# Power_Managment.net
KiCad netlist of a schematic drawn in Altium Designer
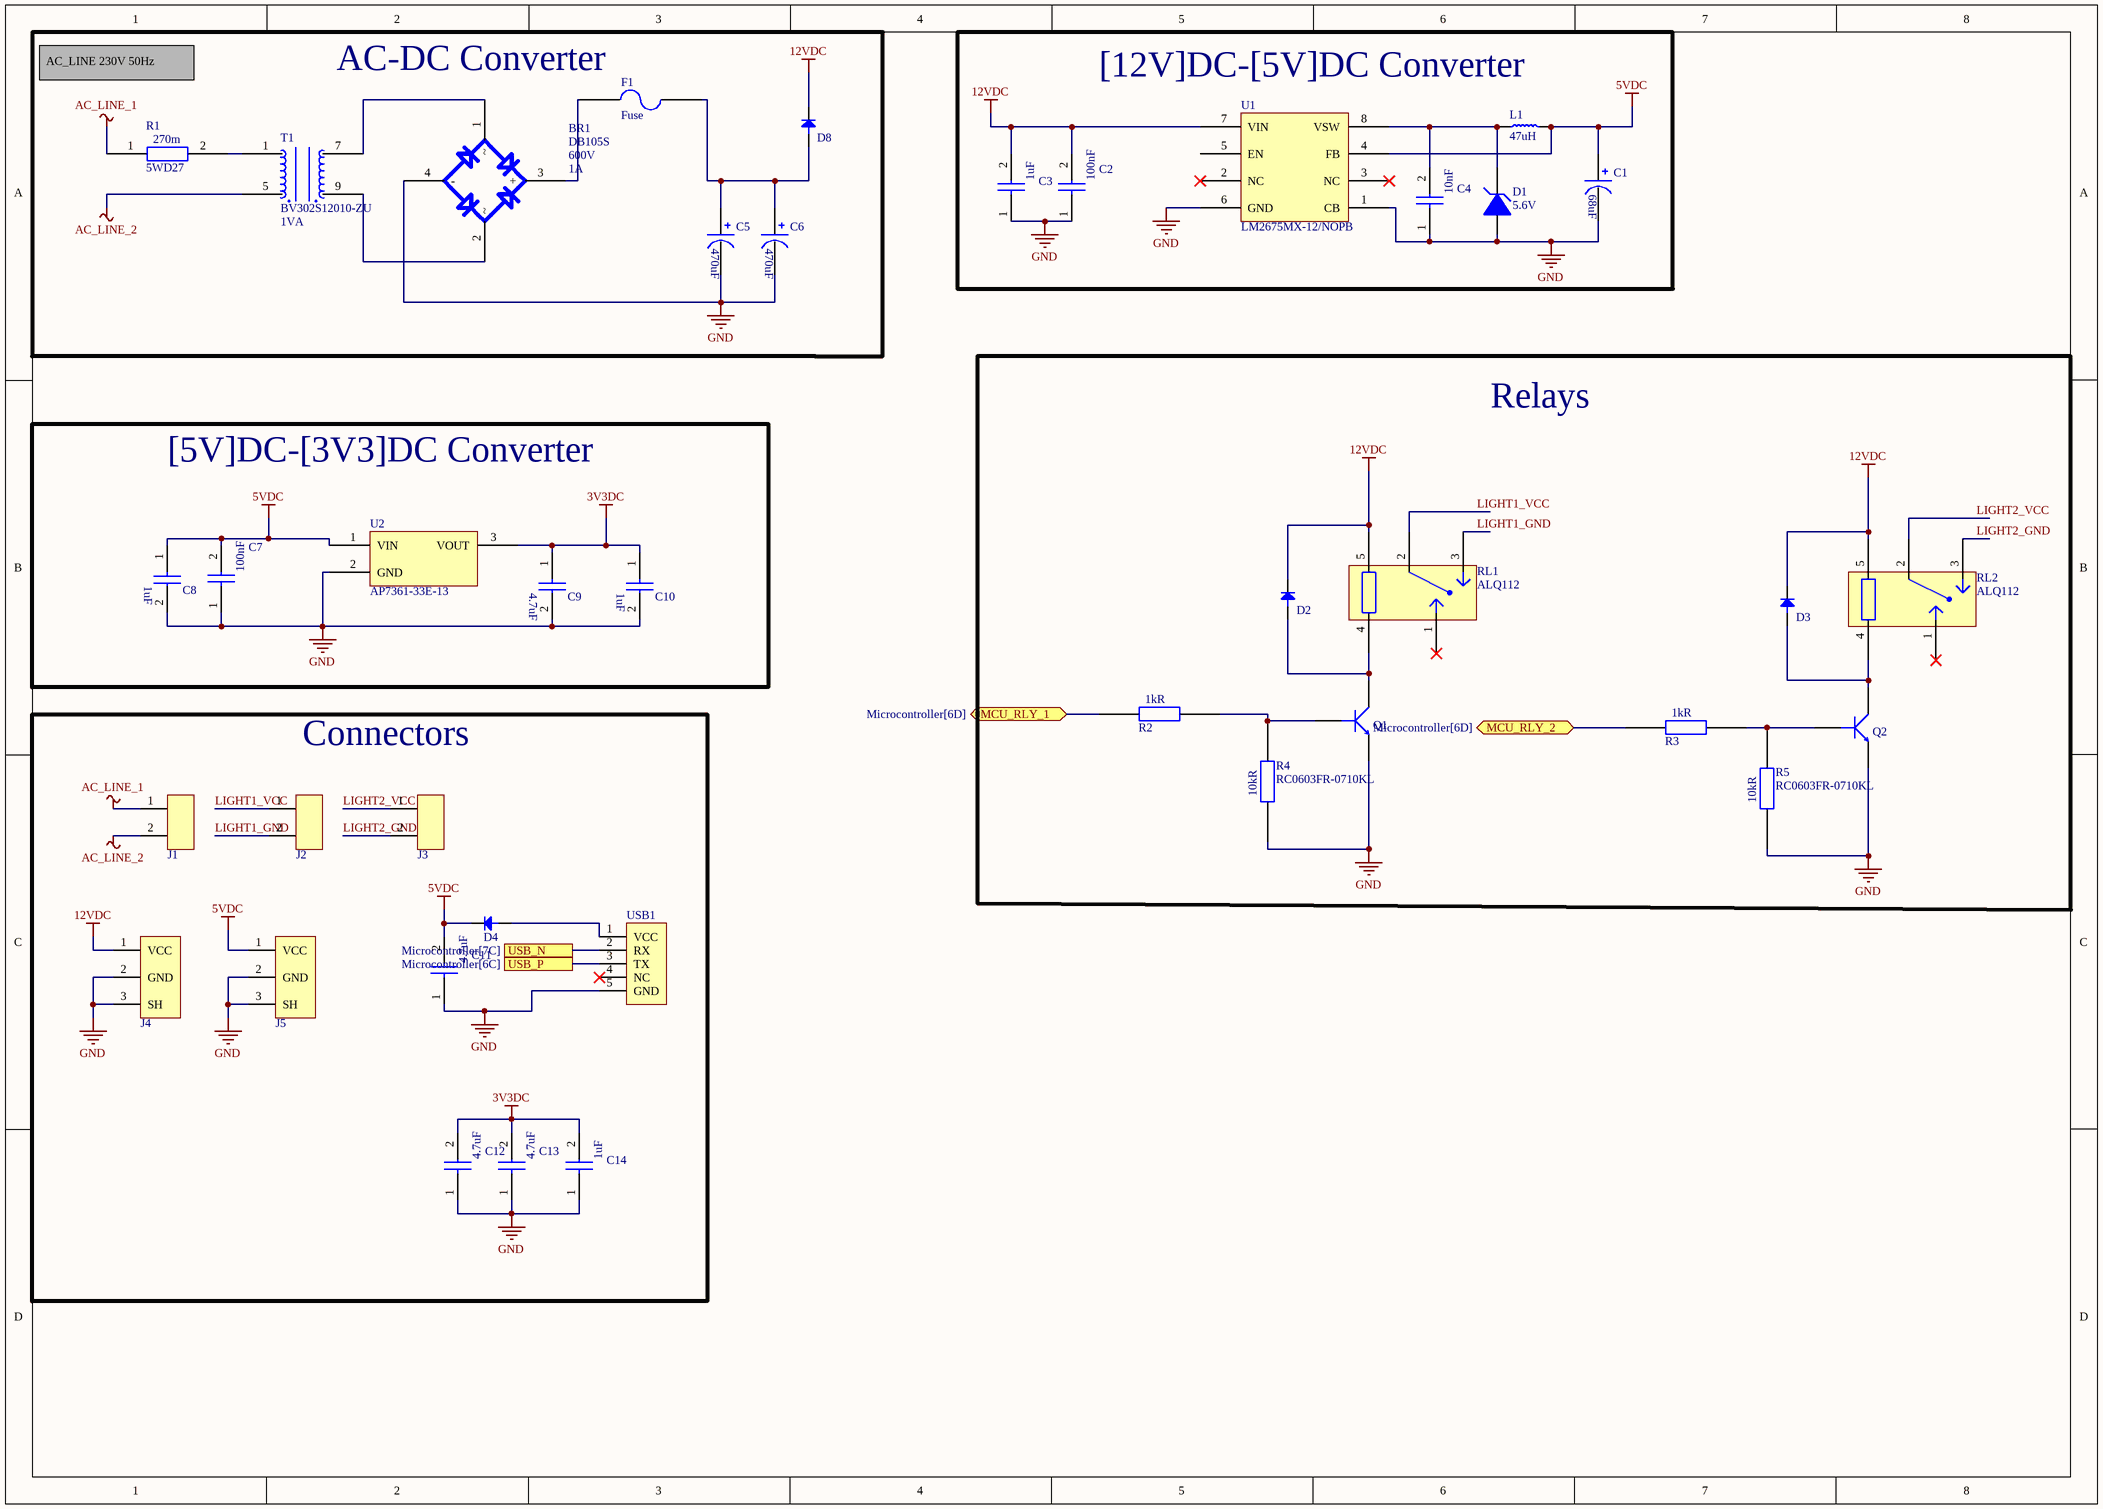
[diagram p0: Power Managment.SchDoc]

(export (version "E")
  (design (tool "Eeschema 10.0.6"))
  (components
    (comp (ref "BR1")
      (value "DB105S")
      (footprint "DB-S")
      (description "Bridge Rect 1PHASE 600V 1A Db-s")
      (fields
        (field (name "MANUFACTURER") "Sangdest Microelectronics")
        (field (name "OPERATION VOLTAGE") "600V")
        (field (name "MAX CURRENT") "1A")
      )
      (libsource (lib "bowtie") (part "DB105S"))
    )
    (comp (ref "C1")
      (value "EEV686M035A9HAA")
      (footprint "EEV 6,3X7,7")
      (description "Cap Aluminum Lytic 68uF 35V 20% (6.3 X 7.7mm) SMD 280mA 2000h 105C T/R")
      (libsource (lib "bowtie") (part "CAP ALU ELEC 68uF 35V %20"))
    )
    (comp (ref "C2")
      (value "CL21B104KBCNNNC")
      (footprint "CAP_0805")
      (description "CAP CER 100nF %10 0603 SMD")
      (fields
        (field (name "MANUFACTURER") "Samsung")
        (field (name "TOLERANCE") "10%")
        (field (name "DESIGNED BY") "BERK")
      )
      (libsource (lib "bowtie") (part "CAP CER 0805 100nF %10"))
    )
    (comp (ref "C3")
      (value "CL21B105KBFNNNE")
      (footprint "CAP_0805")
      (description "CAP CER 1uF %10 0805")
      (fields
        (field (name "MANUFACTURER") "Samsung")
        (field (name "TOLERANCE") "10%")
        (field (name "DESIGNED BY") "BERK")
      )
      (libsource (lib "bowtie") (part "CAP CER 0805 1uF %10"))
    )
    (comp (ref "C4")
      (value "0603B103K160CT")
      (footprint "CAP_0603")
      (description "CAP CER 10nF %10 0603")
      (fields
        (field (name "MANUFACTURER") "Walsin Technologies")
        (field (name "TOLERANCE") "10%")
        (field (name "DESIGNED BY") "BERK")
      )
      (libsource (lib "bowtie") (part "CAP CER 0603 10nF %10"))
    )
    (comp (ref "C5")
      (value "~")
      (footprint "CAP_RADIAL_D10_P5")
      (description "Cap, 470UF, 50V, Alu Elec, Radial")
      (fields
        (field (name "MANUFACTURER") "KEMET")
        (field (name "MANUFACTURER PART NUMBER") "ESH477M050AH4AA")
        (field (name "DESIGNED BY") "Mert Ali Şentürk")
      )
      (libsource (lib "bowtie") (part "CAP ALU ELEC 470uF 50V"))
    )
    (comp (ref "C6")
      (value "~")
      (footprint "CAP_RADIAL_D10_P5")
      (description "Cap, 470UF, 50V, Alu Elec, Radial")
      (fields
        (field (name "MANUFACTURER") "KEMET")
        (field (name "MANUFACTURER PART NUMBER") "ESH477M050AH4AA")
        (field (name "DESIGNED BY") "Mert Ali Şentürk")
      )
      (libsource (lib "bowtie") (part "CAP ALU ELEC 470uF 50V"))
    )
    (comp (ref "C7")
      (value "C0603C104K5RACTU")
      (footprint "CAP_0603")
      (description "Multilayer Ceramic Capacitor, 0.1 uF, 50 V, ± 10%, X7R, 0603 [1608 Metric]")
      (fields
        (field (name "MANUFACTURER") "KEMET")
        (field (name "TOLERANCE") "10%")
        (field (name "DESIGNED BY") "Mert Ali Şentürk")
      )
      (libsource (lib "bowtie") (part "CAP CER 0603 100nF %10"))
    )
    (comp (ref "C8")
      (value "CL21B105KBFNNNE")
      (footprint "CAP_0805")
      (description "CAP CER 1uF %10 0805")
      (fields
        (field (name "MANUFACTURER") "Samsung")
        (field (name "TOLERANCE") "10%")
        (field (name "DESIGNED BY") "BERK")
      )
      (libsource (lib "bowtie") (part "CAP CER 0805 1uF %10"))
    )
    (comp (ref "C9")
      (value "CL21A475KAQNNNE")
      (footprint "CAP_0805")
      (description "CAP CER 4.7uF %10 0805")
      (fields
        (field (name "MANUFACTURER") "Samsung")
        (field (name "TOLERANCE") "10%")
        (field (name "DESIGNED BY") "BERK")
      )
      (libsource (lib "bowtie") (part "CAP CER 0805 4.7uF %10"))
    )
    (comp (ref "C10")
      (value "CL21B105KBFNNNE")
      (footprint "CAP_0805")
      (description "CAP CER 1uF %10 0805")
      (fields
        (field (name "MANUFACTURER") "Samsung")
        (field (name "TOLERANCE") "10%")
        (field (name "DESIGNED BY") "BERK")
      )
      (libsource (lib "bowtie") (part "CAP CER 0805 1uF %10"))
    )
    (comp (ref "C11")
      (value "CL21A475KAQNNNE")
      (footprint "CAP_0805")
      (description "CAP CER 4.7uF %10 0805")
      (fields
        (field (name "MANUFACTURER") "Samsung")
        (field (name "TOLERANCE") "10%")
        (field (name "DESIGNED BY") "BERK")
      )
      (libsource (lib "bowtie") (part "CAP CER 0805 4.7uF %10"))
    )
    (comp (ref "C12")
      (value "CL21A475KAQNNNE")
      (footprint "CAP_0805")
      (description "CAP CER 4.7uF %10 0805")
      (fields
        (field (name "MANUFACTURER") "Samsung")
        (field (name "TOLERANCE") "10%")
        (field (name "DESIGNED BY") "BERK")
      )
      (libsource (lib "bowtie") (part "CAP CER 0805 4.7uF %10"))
    )
    (comp (ref "C13")
      (value "CL21A475KAQNNNE")
      (footprint "CAP_0805")
      (description "CAP CER 4.7uF %10 0805")
      (fields
        (field (name "MANUFACTURER") "Samsung")
        (field (name "TOLERANCE") "10%")
        (field (name "DESIGNED BY") "BERK")
      )
      (libsource (lib "bowtie") (part "CAP CER 0805 4.7uF %10"))
    )
    (comp (ref "C14")
      (value "CL21B105KBFNNNE")
      (footprint "CAP_0805")
      (description "CAP CER 1uF %10 0805")
      (fields
        (field (name "MANUFACTURER") "Samsung")
        (field (name "TOLERANCE") "10%")
        (field (name "DESIGNED BY") "BERK")
      )
      (libsource (lib "bowtie") (part "CAP CER 0805 1uF %10"))
    )
    (comp (ref "D1")
      (value "1SMB5919BT3G")
      (footprint "DO-214AA/SMB")
      (description "Diode Zener Single 5.6V 5% 3W 2-Pin SMB T/R")
      (fields
        (field (name "MANUFACTURER") "ON Semiconductor")
        (field (name "TOLERANCE") "5%")
        (field (name "WORKING VOLTAGE") "5.6V")
        (field (name "DESIGNED BY") "BERK")
      )
      (libsource (lib "bowtie") (part "1SMB5919BT3G"))
    )
    (comp (ref "D2")
      (value "1N4148WS")
      (footprint "SOD-323F")
      (description "Diode, Single, 75 V, 150 mA, 1 V, 4 ns")
      (fields
        (field (name "MANUFACTURER") "ON Semiconductor / Fairchild")
        (field (name "DESIGNED BY") "BERK")
      )
      (libsource (lib "bowtie") (part "1N4148WS"))
    )
    (comp (ref "D3")
      (value "1N4148WS")
      (footprint "SOD-323F")
      (description "Diode, Single, 75 V, 150 mA, 1 V, 4 ns")
      (fields
        (field (name "MANUFACTURER") "ON Semiconductor / Fairchild")
        (field (name "DESIGNED BY") "BERK")
      )
      (libsource (lib "bowtie") (part "1N4148WS"))
    )
    (comp (ref "D4")
      (value "1N4148WS")
      (footprint "SOD-323F")
      (description "Diode, Single, 75 V, 150 mA, 1 V, 4 ns")
      (fields
        (field (name "MANUFACTURER") "ON Semiconductor / Fairchild")
        (field (name "DESIGNED BY") "BERK")
      )
      (libsource (lib "bowtie") (part "1N4148WS"))
    )
    (comp (ref "D8")
      (value "1N4148WS")
      (footprint "SOD-323F")
      (description "Diode, Single, 75 V, 150 mA, 1 V, 4 ns")
      (fields
        (field (name "MANUFACTURER") "ON Semiconductor / Fairchild")
        (field (name "DESIGNED BY") "BERK")
      )
      (libsource (lib "bowtie") (part "1N4148WS"))
    )
    (comp (ref "F1") (value "Fuse") (footprint "3413.0216.22") (libsource (lib "bowtie") (part "Fuse")))
    (comp (ref "J1")
      (value "TBP01R1-508-02BE")
      (footprint "TBP01R1-508")
      (description "Conn Shrouded Header HDR 2 POS 5.08mm Solder RA Side Entry Thru-Hole Bag")
      (fields (field (name "MANUFACTURER") "CUI") (field (name "DESIGNED BY") "BERK"))
      (libsource (lib "bowtie") (part "TBP01R1-508-02BE"))
    )
    (comp (ref "J2")
      (value "TBP01R1-508-02BE")
      (footprint "TBP01R1-508")
      (description "Conn Shrouded Header HDR 2 POS 5.08mm Solder RA Side Entry Thru-Hole Bag")
      (fields (field (name "MANUFACTURER") "CUI") (field (name "DESIGNED BY") "BERK"))
      (libsource (lib "bowtie") (part "TBP01R1-508-02BE"))
    )
    (comp (ref "J3")
      (value "TBP01R1-508-02BE")
      (footprint "TBP01R1-508")
      (description "Conn Shrouded Header HDR 2 POS 5.08mm Solder RA Side Entry Thru-Hole Bag")
      (fields (field (name "MANUFACTURER") "CUI") (field (name "DESIGNED BY") "BERK"))
      (libsource (lib "bowtie") (part "TBP01R1-508-02BE"))
    )
    (comp (ref "J4")
      (value "PJ-037AH-SMT-TR")
      (footprint "JACK")
      (description "DC Power Connectors Power Jacks")
      (fields (field (name "MANUFACTURER") "CUI") (field (name "DESIGNED BY") "BERK"))
      (libsource (lib "bowtie") (part "PJ-037AH-SMT-TR"))
    )
    (comp (ref "J5")
      (value "PJ-037AH-SMT-TR")
      (footprint "JACK")
      (description "DC Power Connectors Power Jacks")
      (fields (field (name "MANUFACTURER") "CUI") (field (name "DESIGNED BY") "BERK"))
      (libsource (lib "bowtie") (part "PJ-037AH-SMT-TR"))
    )
    (comp (ref "L1")
      (value "78438335470")
      (footprint "INDUCTOR 78438335470")
      (description "FIXED IND 47UH 390MA 2.3 OHM SMD")
      (fields
        (field (name "MANUFACTURER") "Wurth Electronics")
        (field (name "TOLERANCE") "30%")
        (field (name "INDUCTANCE") "47uH")
        (field (name "DESIGNED BY") "BERK")
      )
      (libsource (lib "bowtie") (part "IND 47uH"))
    )
    (comp (ref "Q1")
      (value "MMBT3904-7-F")
      (footprint "SOT23-F")
      (description "Transistor General Purpose BJT NPN 40 Volt 0.2A Automotive 3-Pin SOT-23")
      (fields (field (name "MANUFACTURER") "Diodes Zetex") (field (name "DESIGNED BY") "BERK"))
      (libsource (lib "bowtie") (part "MMBT3904-7-F"))
    )
    (comp (ref "Q2")
      (value "MMBT3904-7-F")
      (footprint "SOT23-F")
      (description "Transistor General Purpose BJT NPN 40 Volt 0.2A Automotive 3-Pin SOT-23")
      (fields (field (name "MANUFACTURER") "Diodes Zetex") (field (name "DESIGNED BY") "BERK"))
      (libsource (lib "bowtie") (part "MMBT3904-7-F"))
    )
    (comp (ref "R1")
      (value "5WD27")
      (footprint "RES_AXIAL_W")
      (description "Resistor 5 Watt Cermet Wirewound Flameproof .27 Ohm 5% Axial Lead")
      (libsource (lib "bowtie") (part "5WD27"))
    )
    (comp (ref "R2")
      (value "RC0603FR-0710KL")
      (footprint "RES_0603")
      (description "RES 1K %1 OHM 0603 SMD")
      (fields
        (field (name "MANUFACTURER") "Yageo")
        (field (name "MANUFACTURER PART NUMBER") "RC0603JR-071KL")
        (field (name "DESIGNED BY") "BERK")
      )
      (libsource (lib "bowtie") (part "RES 0603 1kR %1"))
    )
    (comp (ref "R3")
      (value "RC0603FR-0710KL")
      (footprint "RES_0603")
      (description "RES 1K %1 OHM 0603 SMD")
      (fields
        (field (name "MANUFACTURER") "Yageo")
        (field (name "MANUFACTURER PART NUMBER") "RC0603JR-071KL")
        (field (name "DESIGNED BY") "BERK")
      )
      (libsource (lib "bowtie") (part "RES 0603 1kR %1"))
    )
    (comp (ref "R4")
      (value "RC0603FR-0710KL")
      (footprint "RES_0603")
      (description "RES 10K %1 OHM 0603 SMD")
      (fields (field (name "DESIGNED BY") "Mert Ali Şentürk"))
      (libsource (lib "bowtie") (part "RES 0603 10kR %1"))
    )
    (comp (ref "R5")
      (value "RC0603FR-0710KL")
      (footprint "RES_0603")
      (description "RES 10K %1 OHM 0603 SMD")
      (fields (field (name "DESIGNED BY") "Mert Ali Şentürk"))
      (libsource (lib "bowtie") (part "RES 0603 10kR %1"))
    )
    (comp (ref "RL1")
      (value "ALQ112")
      (footprint "ALQ112")
      (description "Electromechanical Relay 12VDC 360Ohm 10(NO)/3(NC)A SPDT (( 20mm 10mm 16mm)) THT Power Relay")
      (fields (field (name "MANUFACTURER") "Panasonic") (field (name "DESIGNED BY") "Mert Ali Şentürk"))
      (libsource (lib "bowtie") (part "ALQ112"))
    )
    (comp (ref "RL2")
      (value "ALQ112")
      (footprint "ALQ112")
      (description "Electromechanical Relay 12VDC 360Ohm 10(NO)/3(NC)A SPDT (( 20mm 10mm 16mm)) THT Power Relay")
      (fields (field (name "MANUFACTURER") "Panasonic") (field (name "DESIGNED BY") "Mert Ali Şentürk"))
      (libsource (lib "bowtie") (part "ALQ112"))
    )
    (comp (ref "T1")
      (value "BV302S12010-ZU")
      (footprint "BV302S12010")
      (description "PWR XFMR LAMINATED 1VA TH")
      (fields (field (name "RATED POWER") "1VA") (field (name "DESIGNED BY") "Mert Ali Şentürk"))
      (libsource (lib "bowtie") (part "BV302S12010-ZU"))
    )
    (comp (ref "U1")
      (value "LM2675MX-12/NOPB")
      (footprint "SOIC-8")
      (description "SIMPLE SWITCHER® 6.5V to 40V, 1A Low Component Count Step-Down Regulator 8-SOIC -40 to 125")
      (fields
        (field (name "MANUFACTURER") "TI National Semiconductor")
        (field (name "DESIGNED BY") "Mert Ali Şentürk")
      )
      (libsource (lib "bowtie") (part "LM2675MX-12/NOPB"))
    )
    (comp (ref "U2")
      (value "AP7361-33E-13")
      (footprint "SOT223")
      (description "AP7361 Series 3.3 V 1 A Low SMT Dropout Fixed-Mode Regulator - SOT-223")
      (fields (field (name "MANUFACTURER") "Diodes") (field (name "DESIGNED BY") "Mert Ali Şentürk"))
      (libsource (lib "bowtie") (part "AP7361-33E-13"))
    )
    (comp (ref "USB1")
      (value "10118192-0001LF")
      (footprint "MICRO_B_USB")
      (description "CONN RCPT USB2.0 MICRO B SMD R/A")
      (libsource (lib "bowtie") (part "Micro B USB Connector"))
    )
  )
  (nets
    (net (code "1") (name "/LIGHT1_GND") (class "Default")
      (node (ref "J2") (pin "2") (pinfunction "2_2") (pintype "power_in"))
      (node (ref "RL1") (pin "3") (pinfunction "3_3") (pintype "passive"))
    )
    (net (code "2") (name "/LIGHT1_VCC") (class "Default")
      (node (ref "J2") (pin "1") (pinfunction "1_1") (pintype "power_in"))
      (node (ref "RL1") (pin "2") (pinfunction "2_2") (pintype "passive"))
    )
    (net (code "3") (name "/LIGHT2_GND") (class "Default")
      (node (ref "J3") (pin "2") (pinfunction "2_2") (pintype "power_in"))
      (node (ref "RL2") (pin "3") (pinfunction "3_3") (pintype "passive"))
    )
    (net (code "4") (name "/LIGHT2_VCC") (class "Default")
      (node (ref "J3") (pin "1") (pinfunction "1_1") (pintype "power_in"))
      (node (ref "RL2") (pin "2") (pinfunction "2_2") (pintype "passive"))
    )
    (net (code "5") (name "/MCU_RLY_1") (class "Default")
      (node (ref "R2") (pin "1") (pinfunction "1_1") (pintype "passive"))
    )
    (net (code "6") (name "/MCU_RLY_2") (class "Default")
      (node (ref "R3") (pin "1") (pinfunction "1_1") (pintype "passive"))
    )
    (net (code "7") (name "/USB_N") (class "Default")
      (node (ref "USB1") (pin "2") (pinfunction "RX_2") (pintype "passive"))
    )
    (net (code "8") (name "/USB_P") (class "Default")
      (node (ref "USB1") (pin "3") (pinfunction "TX_3") (pintype "passive"))
    )
    (net (code "9") (name "3V3DC") (class "Default")
      (node (ref "C10") (pin "1") (pinfunction "1_1") (pintype "passive"))
      (node (ref "C12") (pin "2") (pinfunction "2_2") (pintype "passive"))
      (node (ref "C13") (pin "2") (pinfunction "2_2") (pintype "passive"))
      (node (ref "C14") (pin "2") (pinfunction "2_2") (pintype "passive"))
      (node (ref "C9") (pin "1") (pinfunction "1_1") (pintype "passive"))
      (node (ref "U2") (pin "3") (pinfunction "VOUT_3") (pintype "passive"))
    )
    (net (code "10") (name "5VDC") (class "Default")
      (node (ref "C1") (pin "1") (pinfunction "1_1") (pintype "passive"))
      (node (ref "C11") (pin "2") (pinfunction "2_2") (pintype "passive"))
      (node (ref "C7") (pin "2") (pinfunction "2_2") (pintype "passive"))
      (node (ref "C8") (pin "1") (pinfunction "1_1") (pintype "passive"))
      (node (ref "D4") (pin "1") (pinfunction "1_1") (pintype "passive"))
      (node (ref "J5") (pin "1") (pinfunction "VCC_1") (pintype "power_in"))
      (node (ref "L1") (pin "2") (pinfunction "2_2") (pintype "passive"))
      (node (ref "U1") (pin "4") (pinfunction "FB_4") (pintype "passive"))
      (node (ref "U2") (pin "1") (pinfunction "VIN_1") (pintype "passive"))
    )
    (net (code "11") (name "12VDC") (class "Default")
      (node (ref "C2") (pin "2") (pinfunction "2_2") (pintype "passive"))
      (node (ref "C3") (pin "2") (pinfunction "2_2") (pintype "passive"))
      (node (ref "D2") (pin "1") (pinfunction "1_1") (pintype "passive"))
      (node (ref "D3") (pin "1") (pinfunction "1_1") (pintype "passive"))
      (node (ref "D8") (pin "1") (pinfunction "1_1") (pintype "passive"))
      (node (ref "J4") (pin "1") (pinfunction "VCC_1") (pintype "power_in"))
      (node (ref "RL1") (pin "5") (pinfunction "5_5") (pintype "passive"))
      (node (ref "RL2") (pin "5") (pinfunction "5_5") (pintype "passive"))
      (node (ref "U1") (pin "7") (pinfunction "VIN_7") (pintype "passive"))
    )
    (net (code "12") (name "AC_LINE_1") (class "Default")
      (node (ref "J1") (pin "1") (pinfunction "1_1") (pintype "power_in"))
      (node (ref "R1") (pin "1") (pinfunction "1_1") (pintype "passive"))
    )
    (net (code "13") (name "AC_LINE_2") (class "Default")
      (node (ref "J1") (pin "2") (pinfunction "2_2") (pintype "power_in"))
      (node (ref "T1") (pin "5") (pinfunction "5_5") (pintype "passive"))
    )
    (net (code "14") (name "GND") (class "Default")
      (node (ref "BR1") (pin "4") (pinfunction "-_4") (pintype "passive"))
      (node (ref "C1") (pin "2") (pinfunction "2_2") (pintype "passive"))
      (node (ref "C10") (pin "2") (pinfunction "2_2") (pintype "passive"))
      (node (ref "C11") (pin "1") (pinfunction "1_1") (pintype "passive"))
      (node (ref "C12") (pin "1") (pinfunction "1_1") (pintype "passive"))
      (node (ref "C13") (pin "1") (pinfunction "1_1") (pintype "passive"))
      (node (ref "C14") (pin "1") (pinfunction "1_1") (pintype "passive"))
      (node (ref "C2") (pin "1") (pinfunction "1_1") (pintype "passive"))
      (node (ref "C3") (pin "1") (pinfunction "1_1") (pintype "passive"))
      (node (ref "C4") (pin "1") (pinfunction "1_1") (pintype "passive"))
      (node (ref "C5") (pin "2") (pinfunction "2_2") (pintype "passive"))
      (node (ref "C6") (pin "2") (pinfunction "2_2") (pintype "passive"))
      (node (ref "C7") (pin "1") (pinfunction "1_1") (pintype "passive"))
      (node (ref "C8") (pin "2") (pinfunction "2_2") (pintype "passive"))
      (node (ref "C9") (pin "2") (pinfunction "2_2") (pintype "passive"))
      (node (ref "D1") (pin "2") (pinfunction "2_2") (pintype "passive"))
      (node (ref "J4") (pin "2") (pinfunction "GND_2") (pintype "power_in"))
      (node (ref "J4") (pin "3") (pinfunction "SH_3") (pintype "power_in"))
      (node (ref "J5") (pin "2") (pinfunction "GND_2") (pintype "power_in"))
      (node (ref "J5") (pin "3") (pinfunction "SH_3") (pintype "power_in"))
      (node (ref "Q1") (pin "2") (pinfunction "E_2") (pintype "power_in"))
      (node (ref "Q2") (pin "2") (pinfunction "E_2") (pintype "power_in"))
      (node (ref "R4") (pin "1") (pinfunction "1_1") (pintype "passive"))
      (node (ref "R5") (pin "1") (pinfunction "1_1") (pintype "passive"))
      (node (ref "U1") (pin "1") (pinfunction "CB_1") (pintype "passive"))
      (node (ref "U1") (pin "6") (pinfunction "GND_6") (pintype "passive"))
      (node (ref "U2") (pin "2") (pinfunction "GND_2") (pintype "passive"))
      (node (ref "USB1") (pin "5") (pinfunction "GND_5") (pintype "passive"))
    )
    (net (code "15") (name "Net-(BR1-+)") (class "Default")
      (node (ref "BR1") (pin "3") (pinfunction "+_3") (pintype "passive"))
      (node (ref "F1") (pin "1") (pinfunction "1_1") (pintype "passive"))
    )
    (net (code "16") (name "Net-(BR1-~-Pad1)") (class "Default")
      (node (ref "BR1") (pin "1") (pinfunction "~_1") (pintype "passive"))
      (node (ref "T1") (pin "7") (pinfunction "7_7") (pintype "passive"))
    )
    (net (code "17") (name "Net-(BR1-~-Pad2)") (class "Default")
      (node (ref "BR1") (pin "2") (pinfunction "~_2") (pintype "passive"))
      (node (ref "T1") (pin "9") (pinfunction "9_9") (pintype "passive"))
    )
    (net (code "18") (name "Net-(C5-Pad1)") (class "Default")
      (node (ref "C5") (pin "1") (pinfunction "1_1") (pintype "passive"))
      (node (ref "C6") (pin "1") (pinfunction "1_1") (pintype "passive"))
      (node (ref "D8") (pin "2") (pinfunction "2_2") (pintype "passive"))
      (node (ref "F1") (pin "2") (pinfunction "2_2") (pintype "passive"))
    )
    (net (code "19") (name "Net-(Q1-B)") (class "Default")
      (node (ref "Q1") (pin "1") (pinfunction "B_1") (pintype "power_in"))
      (node (ref "R2") (pin "2") (pinfunction "2_2") (pintype "passive"))
      (node (ref "R4") (pin "2") (pinfunction "2_2") (pintype "passive"))
    )
    (net (code "20") (name "Net-(Q1-C)") (class "Default")
      (node (ref "D2") (pin "2") (pinfunction "2_2") (pintype "passive"))
      (node (ref "Q1") (pin "3") (pinfunction "C_3") (pintype "power_in"))
      (node (ref "RL1") (pin "4") (pinfunction "4_4") (pintype "passive"))
    )
    (net (code "21") (name "Net-(Q2-B)") (class "Default")
      (node (ref "Q2") (pin "1") (pinfunction "B_1") (pintype "power_in"))
      (node (ref "R3") (pin "2") (pinfunction "2_2") (pintype "passive"))
      (node (ref "R5") (pin "2") (pinfunction "2_2") (pintype "passive"))
    )
    (net (code "22") (name "Net-(Q2-C)") (class "Default")
      (node (ref "D3") (pin "2") (pinfunction "2_2") (pintype "passive"))
      (node (ref "Q2") (pin "3") (pinfunction "C_3") (pintype "power_in"))
      (node (ref "RL2") (pin "4") (pinfunction "4_4") (pintype "passive"))
    )
    (net (code "23") (name "Net-(R1-Pad2)") (class "Default")
      (node (ref "R1") (pin "2") (pinfunction "2_2") (pintype "passive"))
      (node (ref "T1") (pin "1") (pinfunction "1_1") (pintype "passive"))
    )
    (net (code "24") (name "Net-(U1-VSW)") (class "Default")
      (node (ref "C4") (pin "2") (pinfunction "2_2") (pintype "passive"))
      (node (ref "D1") (pin "1") (pinfunction "1_1") (pintype "passive"))
      (node (ref "L1") (pin "1") (pinfunction "1_1") (pintype "passive"))
      (node (ref "U1") (pin "8") (pinfunction "VSW_8") (pintype "passive"))
    )
    (net (code "25") (name "Net-(USB1-VCC)") (class "Default")
      (node (ref "D4") (pin "2") (pinfunction "2_2") (pintype "passive"))
      (node (ref "USB1") (pin "1") (pinfunction "VCC_1") (pintype "passive"))
    )
    (net (code "26") (name "unconnected-(RL1-Pad1)") (class "Default")
      (node (ref "RL1") (pin "1") (pinfunction "1_1") (pintype "passive+no_connect"))
    )
    (net (code "27") (name "unconnected-(RL2-Pad1)") (class "Default")
      (node (ref "RL2") (pin "1") (pinfunction "1_1") (pintype "passive+no_connect"))
    )
    (net (code "28") (name "unconnected-(U1-EN-Pad5)") (class "Default")
      (node (ref "U1") (pin "5") (pinfunction "EN_5") (pintype "passive"))
    )
    (net (code "29") (name "unconnected-(U1-NC-Pad2)") (class "Default")
      (node (ref "U1") (pin "2") (pinfunction "NC_2") (pintype "passive+no_connect"))
    )
    (net (code "30") (name "unconnected-(U1-NC-Pad3)") (class "Default")
      (node (ref "U1") (pin "3") (pinfunction "NC_3") (pintype "passive+no_connect"))
    )
    (net (code "31") (name "unconnected-(USB1-NC-Pad4)") (class "Default")
      (node (ref "USB1") (pin "4") (pinfunction "NC_4") (pintype "passive+no_connect"))
    )
  )
)
